# SENSE_DAC_-_8CH.net
KiCad netlist of a schematic drawn in Altium Designer
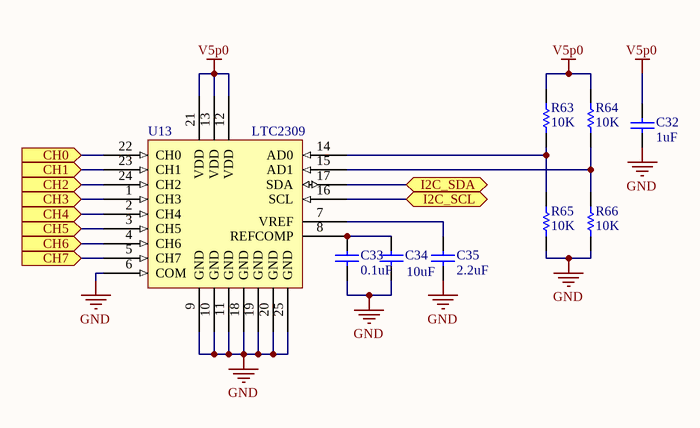
[diagram p0: SENSE DAC - 8CH.SchDoc]

(export (version "E")
  (design (tool "Eeschema 10.0.6"))
  (components
    (comp (ref "C32")
      (value "1uF")
      (footprint "CAPC01005(0402)22_N")
      (fields (field (name "Comment") "CAP, 0402, 1uF"))
      (libsource (lib "Components") (part "CAP, 0402, 1uF"))
    )
    (comp (ref "C33")
      (value "0.1uF")
      (footprint "CAPC01005(0402)22_N")
      (fields (field (name "Comment") "CAP, 0402, 0.1uF"))
      (libsource (lib "Components") (part "CAP, 0402, 0.1uF"))
    )
    (comp (ref "C34")
      (value "10uF")
      (footprint "CAPC0805(2012)130_N")
      (fields (field (name "Comment") "CAP, 0805, 10uF"))
      (libsource (lib "Components") (part "CAP, 0805, 10uF"))
    )
    (comp (ref "C35")
      (value "2.2uF")
      (footprint "CAPC01005(0402)22_N")
      (fields (field (name "Comment") "CAP, 0402, 2.2uF"))
      (libsource (lib "Components") (part "CAP, 0402, 2.2uF"))
    )
    (comp (ref "R63")
      (value "10K")
      (footprint "RES, 0603")
      (description "Resistor, 0603, 1/10W, 10K ohm")
      (fields
        (field (name "MANUFACTURER") "Panasonic Electronic Components")
        (field (name "MANUFACTURER PART NUMBER") "ERJ-3EKF1002V")
      )
      (libsource (lib "Resistors0603") (part "RES_0603_10K"))
    )
    (comp (ref "R64")
      (value "10K")
      (footprint "RES, 0603")
      (description "Resistor, 0603, 1/10W, 10K ohm")
      (fields
        (field (name "MANUFACTURER") "Panasonic Electronic Components")
        (field (name "MANUFACTURER PART NUMBER") "ERJ-3EKF1002V")
      )
      (libsource (lib "Resistors0603") (part "RES_0603_10K"))
    )
    (comp (ref "R65")
      (value "10K")
      (footprint "RES, 0603")
      (description "Resistor, 0603, 1/10W, 10K ohm")
      (fields
        (field (name "MANUFACTURER") "Panasonic Electronic Components")
        (field (name "MANUFACTURER PART NUMBER") "ERJ-3EKF1002V")
      )
      (libsource (lib "Resistors0603") (part "RES_0603_10K"))
    )
    (comp (ref "R66")
      (value "10K")
      (footprint "RES, 0603")
      (description "Resistor, 0603, 1/10W, 10K ohm")
      (fields
        (field (name "MANUFACTURER") "Panasonic Electronic Components")
        (field (name "MANUFACTURER PART NUMBER") "ERJ-3EKF1002V")
      )
      (libsource (lib "Resistors0603") (part "RES_0603_10K"))
    )
    (comp (ref "U13")
      (value "LTC2309")
      (footprint "QFN50P400X400X80-24N")
      (description "8-Channel, 12-Bit SAR ADC with I2C Interface")
      (fields
        (field (name "MANUFACTURER") "Linear Technology")
        (field (name "MANUFACTURER PART NUMBER") "LTC2309CUF#PBF")
      )
      (libsource (lib "Components") (part "LTC2309"))
    )
  )
  (nets
    (net (code "1") (name "/CH0") (class "Default")
      (node (ref "U13") (pin "22") (pinfunction "CH0_22") (pintype "input"))
    )
    (net (code "2") (name "/CH1") (class "Default")
      (node (ref "U13") (pin "23") (pinfunction "CH1_23") (pintype "input"))
    )
    (net (code "3") (name "/CH2") (class "Default")
      (node (ref "U13") (pin "24") (pinfunction "CH2_24") (pintype "input"))
    )
    (net (code "4") (name "/CH3") (class "Default")
      (node (ref "U13") (pin "1") (pinfunction "CH3_1") (pintype "input"))
    )
    (net (code "5") (name "/CH4") (class "Default")
      (node (ref "U13") (pin "2") (pinfunction "CH4_2") (pintype "input"))
    )
    (net (code "6") (name "/CH5") (class "Default")
      (node (ref "U13") (pin "3") (pinfunction "CH5_3") (pintype "input"))
    )
    (net (code "7") (name "/CH6") (class "Default")
      (node (ref "U13") (pin "4") (pinfunction "CH6_4") (pintype "input"))
    )
    (net (code "8") (name "/CH7") (class "Default")
      (node (ref "U13") (pin "5") (pinfunction "CH7_5") (pintype "input"))
    )
    (net (code "9") (name "/I2C_SCL") (class "Default")
      (node (ref "U13") (pin "16") (pinfunction "SCL_16") (pintype "input"))
    )
    (net (code "10") (name "/I2C_SDA") (class "Default")
      (node (ref "U13") (pin "17") (pinfunction "SDA_17") (pintype "bidirectional"))
    )
    (net (code "11") (name "GND") (class "Default")
      (node (ref "C32") (pin "1") (pinfunction "1_1") (pintype "passive"))
      (node (ref "C33") (pin "1") (pinfunction "1_1") (pintype "passive"))
      (node (ref "C34") (pin "1") (pinfunction "1_1") (pintype "passive"))
      (node (ref "C35") (pin "1") (pinfunction "1_1") (pintype "passive"))
      (node (ref "R65") (pin "2") (pinfunction "2_2") (pintype "passive"))
      (node (ref "R66") (pin "2") (pinfunction "2_2") (pintype "passive"))
      (node (ref "U13") (pin "10") (pinfunction "GND_10") (pintype "power_in"))
      (node (ref "U13") (pin "11") (pinfunction "GND_11") (pintype "power_in"))
      (node (ref "U13") (pin "18") (pinfunction "GND_18") (pintype "power_in"))
      (node (ref "U13") (pin "19") (pinfunction "GND_19") (pintype "power_in"))
      (node (ref "U13") (pin "20") (pinfunction "GND_20") (pintype "power_in"))
      (node (ref "U13") (pin "25") (pinfunction "GND_25") (pintype "power_in"))
      (node (ref "U13") (pin "6") (pinfunction "COM_6") (pintype "input"))
      (node (ref "U13") (pin "9") (pinfunction "GND_9") (pintype "power_in"))
    )
    (net (code "12") (name "Net-(U13-AD0)") (class "Default")
      (node (ref "R63") (pin "2") (pinfunction "2_2") (pintype "passive"))
      (node (ref "R65") (pin "1") (pinfunction "1_1") (pintype "passive"))
      (node (ref "U13") (pin "14") (pinfunction "AD0_14") (pintype "input"))
    )
    (net (code "13") (name "Net-(U13-AD1)") (class "Default")
      (node (ref "R64") (pin "2") (pinfunction "2_2") (pintype "passive"))
      (node (ref "R66") (pin "1") (pinfunction "1_1") (pintype "passive"))
      (node (ref "U13") (pin "15") (pinfunction "AD1_15") (pintype "input"))
    )
    (net (code "14") (name "Net-(U13-REFCOMP)") (class "Default")
      (node (ref "C33") (pin "2") (pinfunction "2_2") (pintype "passive"))
      (node (ref "C34") (pin "2") (pinfunction "2_2") (pintype "passive"))
      (node (ref "U13") (pin "8") (pinfunction "REFCOMP_8") (pintype "passive"))
    )
    (net (code "15") (name "Net-(U13-VREF)") (class "Default")
      (node (ref "C35") (pin "2") (pinfunction "2_2") (pintype "passive"))
      (node (ref "U13") (pin "7") (pinfunction "VREF_7") (pintype "passive"))
    )
    (net (code "16") (name "V5p0") (class "Default")
      (node (ref "C32") (pin "2") (pinfunction "2_2") (pintype "passive"))
      (node (ref "R63") (pin "1") (pinfunction "1_1") (pintype "passive"))
      (node (ref "R64") (pin "1") (pinfunction "1_1") (pintype "passive"))
      (node (ref "U13") (pin "12") (pinfunction "VDD_12") (pintype "power_in"))
      (node (ref "U13") (pin "13") (pinfunction "VDD_13") (pintype "power_in"))
      (node (ref "U13") (pin "21") (pinfunction "VDD_21") (pintype "power_in"))
    )
  )
)
